# SPTSquidBoard.net
KiCad netlist of a schematic drawn in Altium Designer
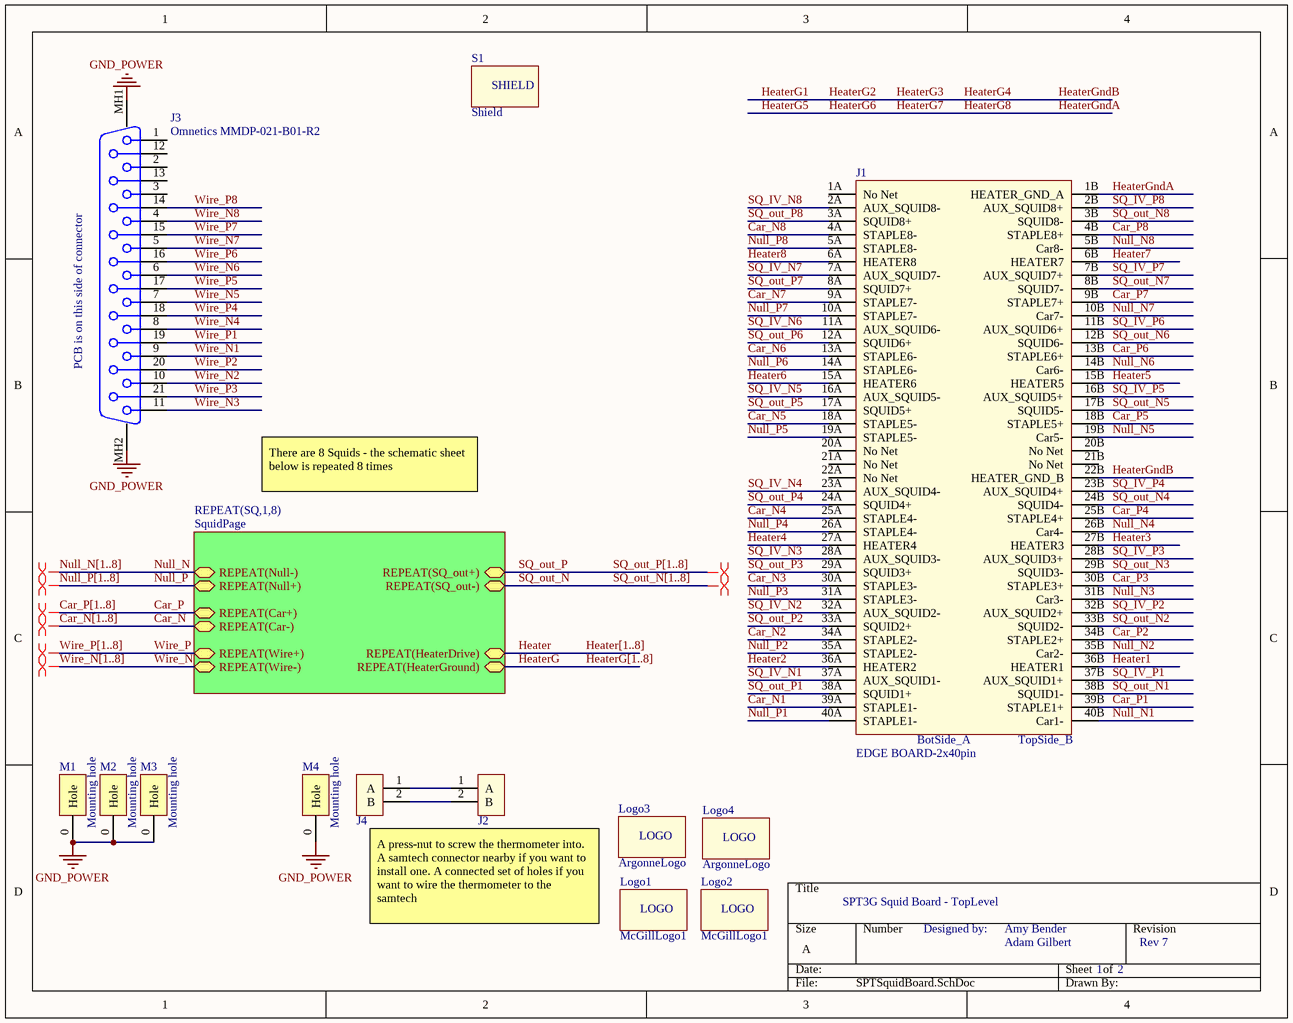
[diagram p0: SPTSquidBoard.SchDoc]

(export (version "E")
  (design (tool "Eeschema 10.0.6"))
  (components
    (comp (ref "J1")
      (value "EDGE BOARD-2x40pin")
      (description "Edge connector")
      (libsource (lib "SPT3G_LCBoard") (part "EDGE BOARD-2x40pin"))
    )
    (comp (ref "J2")
      (value "TempSenseWireConnection")
      (footprint "TempSenseWireCons")
      (libsource (lib "SPT3G_LCBoard") (part "TempSenseCon"))
    )
    (comp (ref "J3")
      (value "Omnetics MMDP-021-B01-R2")
      (footprint "MMDP-021-B02-R2")
      (description "OmneticsMicroD21")
      (libsource (lib "SPT3G_LCBoard") (part "OmneticsMicroD21"))
    )
    (comp (ref "J4")
      (value "TempSenseWireConnection")
      (footprint "TempSenseWireCons")
      (libsource (lib "") (part "TempSenseCon_1"))
    )
    (comp (ref "Logo1")
      (value "McGillLogo1")
      (footprint "McGillLogo1")
      (libsource (lib "SPT3G_LCBoard") (part "Logo"))
    )
    (comp (ref "Logo2")
      (value "McGillLogo1")
      (footprint "McGillLogo1")
      (libsource (lib "SPT3G_LCBoard") (part "Logo"))
    )
    (comp (ref "Logo3")
      (value "ArgonneLogo")
      (footprint "ArgonneLogo")
      (libsource (lib "SPT3G_AdapterBoard") (part "Logo"))
    )
    (comp (ref "Logo4")
      (value "ArgonneLogo")
      (footprint "ArgonneLogo")
      (libsource (lib "SPT3G_AdapterBoard") (part "Logo"))
    )
    (comp (ref "M1")
      (value "Mounting hole")
      (footprint "MountingHoleSquidBoard")
      (libsource (lib "SPT3G_LCBoard") (part "SquidBoardMountingHole"))
    )
    (comp (ref "M2")
      (value "Mounting hole")
      (footprint "MountingHoleSquidBoard")
      (libsource (lib "SPT3G_LCBoard") (part "SquidBoardMountingHole"))
    )
    (comp (ref "M3")
      (value "Mounting hole")
      (footprint "MountingHoleSquidBoard")
      (libsource (lib "SPT3G_LCBoard") (part "SquidBoardMountingHole"))
    )
    (comp (ref "M4")
      (value "Mounting hole")
      (footprint "MountingHoleSquidBoard")
      (libsource (lib "SPT3G_LCBoard") (part "SquidBoardMountingHole"))
    )
    (comp (ref "S1") (value "Shield") (footprint "Shield") (libsource (lib "SPT3G_LCBoard") (part "Shield")))
  )
  (nets
    (net (code "2") (name "/Car_N1") (class "Default")
      (node (ref "J1") (pin "39A") (pinfunction "STAPLE1-_39A") (pintype "passive"))
    )
    (net (code "3") (name "/Car_N2") (class "Default")
      (node (ref "J1") (pin "34A") (pinfunction "STAPLE2-_34A") (pintype "passive"))
    )
    (net (code "4") (name "/Car_N3") (class "Default")
      (node (ref "J1") (pin "30A") (pinfunction "STAPLE3-_30A") (pintype "passive"))
    )
    (net (code "5") (name "/Car_N4") (class "Default")
      (node (ref "J1") (pin "25A") (pinfunction "STAPLE4-_25A") (pintype "passive"))
    )
    (net (code "6") (name "/Car_N5") (class "Default")
      (node (ref "J1") (pin "18A") (pinfunction "STAPLE5-_18A") (pintype "passive"))
    )
    (net (code "7") (name "/Car_N6") (class "Default")
      (node (ref "J1") (pin "13A") (pinfunction "STAPLE6-_13A") (pintype "passive"))
    )
    (net (code "8") (name "/Car_N7") (class "Default")
      (node (ref "J1") (pin "9A") (pinfunction "STAPLE7-_9A") (pintype "passive"))
    )
    (net (code "9") (name "/Car_N8") (class "Default")
      (node (ref "J1") (pin "4A") (pinfunction "STAPLE8-_4A") (pintype "passive"))
    )
    (net (code "12") (name "/Car_P1") (class "Default")
      (node (ref "J1") (pin "39B") (pinfunction "STAPLE1+_39B") (pintype "passive"))
    )
    (net (code "13") (name "/Car_P2") (class "Default")
      (node (ref "J1") (pin "34B") (pinfunction "STAPLE2+_34B") (pintype "passive"))
    )
    (net (code "14") (name "/Car_P3") (class "Default")
      (node (ref "J1") (pin "30B") (pinfunction "STAPLE3+_30B") (pintype "passive"))
    )
    (net (code "15") (name "/Car_P4") (class "Default")
      (node (ref "J1") (pin "25B") (pinfunction "STAPLE4+_25B") (pintype "passive"))
    )
    (net (code "16") (name "/Car_P5") (class "Default")
      (node (ref "J1") (pin "18B") (pinfunction "STAPLE5+_18B") (pintype "passive"))
    )
    (net (code "17") (name "/Car_P6") (class "Default")
      (node (ref "J1") (pin "13B") (pinfunction "STAPLE6+_13B") (pintype "passive"))
    )
    (net (code "18") (name "/Car_P7") (class "Default")
      (node (ref "J1") (pin "9B") (pinfunction "STAPLE7+_9B") (pintype "passive"))
    )
    (net (code "19") (name "/Car_P8") (class "Default")
      (node (ref "J1") (pin "4B") (pinfunction "STAPLE8+_4B") (pintype "passive"))
    )
    (net (code "22") (name "/Heater1") (class "Default")
      (node (ref "J1") (pin "36B") (pinfunction "HEATER1_36B") (pintype "passive"))
    )
    (net (code "23") (name "/Heater2") (class "Default")
      (node (ref "J1") (pin "36A") (pinfunction "HEATER2_36A") (pintype "passive"))
    )
    (net (code "24") (name "/Heater3") (class "Default")
      (node (ref "J1") (pin "27B") (pinfunction "HEATER3_27B") (pintype "passive"))
    )
    (net (code "25") (name "/Heater4") (class "Default")
      (node (ref "J1") (pin "27A") (pinfunction "HEATER4_27A") (pintype "passive"))
    )
    (net (code "26") (name "/Heater5") (class "Default")
      (node (ref "J1") (pin "15B") (pinfunction "HEATER5_15B") (pintype "passive"))
    )
    (net (code "27") (name "/Heater6") (class "Default")
      (node (ref "J1") (pin "15A") (pinfunction "HEATER6_15A") (pintype "passive"))
    )
    (net (code "28") (name "/Heater7") (class "Default")
      (node (ref "J1") (pin "6B") (pinfunction "HEATER7_6B") (pintype "passive"))
    )
    (net (code "29") (name "/Heater8") (class "Default")
      (node (ref "J1") (pin "6A") (pinfunction "HEATER8_6A") (pintype "passive"))
    )
    (net (code "31") (name "/HeaterG4") (class "Default")
      (node (ref "J1") (pin "22B") (pinfunction "HEATER_GND_B_22B") (pintype "passive"))
    )
    (net (code "32") (name "/HeaterG8") (class "Default")
      (node (ref "J1") (pin "1B") (pinfunction "HEATER_GND_A_1B") (pintype "passive"))
    )
    (net (code "36") (name "/Null_N1") (class "Default")
      (node (ref "J1") (pin "40B") (pinfunction "Car1-_40B") (pintype "passive"))
    )
    (net (code "37") (name "/Null_N2") (class "Default")
      (node (ref "J1") (pin "35B") (pinfunction "Car2-_35B") (pintype "passive"))
    )
    (net (code "38") (name "/Null_N3") (class "Default")
      (node (ref "J1") (pin "31B") (pinfunction "Car3-_31B") (pintype "passive"))
    )
    (net (code "39") (name "/Null_N4") (class "Default")
      (node (ref "J1") (pin "26B") (pinfunction "Car4-_26B") (pintype "passive"))
    )
    (net (code "40") (name "/Null_N5") (class "Default")
      (node (ref "J1") (pin "19B") (pinfunction "Car5-_19B") (pintype "passive"))
    )
    (net (code "41") (name "/Null_N6") (class "Default")
      (node (ref "J1") (pin "14B") (pinfunction "Car6-_14B") (pintype "passive"))
    )
    (net (code "42") (name "/Null_N7") (class "Default")
      (node (ref "J1") (pin "10B") (pinfunction "Car7-_10B") (pintype "passive"))
    )
    (net (code "43") (name "/Null_N8") (class "Default")
      (node (ref "J1") (pin "5B") (pinfunction "Car8-_5B") (pintype "passive"))
    )
    (net (code "46") (name "/Null_P1") (class "Default")
      (node (ref "J1") (pin "40A") (pinfunction "STAPLE1-_40A") (pintype "passive"))
    )
    (net (code "47") (name "/Null_P2") (class "Default")
      (node (ref "J1") (pin "35A") (pinfunction "STAPLE2-_35A") (pintype "passive"))
    )
    (net (code "48") (name "/Null_P3") (class "Default")
      (node (ref "J1") (pin "31A") (pinfunction "STAPLE3-_31A") (pintype "passive"))
    )
    (net (code "49") (name "/Null_P4") (class "Default")
      (node (ref "J1") (pin "26A") (pinfunction "STAPLE4-_26A") (pintype "passive"))
    )
    (net (code "50") (name "/Null_P5") (class "Default")
      (node (ref "J1") (pin "19A") (pinfunction "STAPLE5-_19A") (pintype "passive"))
    )
    (net (code "51") (name "/Null_P6") (class "Default")
      (node (ref "J1") (pin "14A") (pinfunction "STAPLE6-_14A") (pintype "passive"))
    )
    (net (code "52") (name "/Null_P7") (class "Default")
      (node (ref "J1") (pin "10A") (pinfunction "STAPLE7-_10A") (pintype "passive"))
    )
    (net (code "53") (name "/Null_P8") (class "Default")
      (node (ref "J1") (pin "5A") (pinfunction "STAPLE8-_5A") (pintype "passive"))
    )
    (net (code "55") (name "/SQ_IV_N1") (class "Default")
      (node (ref "J1") (pin "37A") (pinfunction "AUX_SQUID1-_37A") (pintype "passive"))
    )
    (net (code "56") (name "/SQ_IV_N2") (class "Default")
      (node (ref "J1") (pin "32A") (pinfunction "AUX_SQUID2-_32A") (pintype "passive"))
    )
    (net (code "57") (name "/SQ_IV_N3") (class "Default")
      (node (ref "J1") (pin "28A") (pinfunction "AUX_SQUID3-_28A") (pintype "passive"))
    )
    (net (code "58") (name "/SQ_IV_N4") (class "Default")
      (node (ref "J1") (pin "23A") (pinfunction "AUX_SQUID4-_23A") (pintype "passive"))
    )
    (net (code "59") (name "/SQ_IV_N5") (class "Default")
      (node (ref "J1") (pin "16A") (pinfunction "AUX_SQUID5-_16A") (pintype "passive"))
    )
    (net (code "60") (name "/SQ_IV_N6") (class "Default")
      (node (ref "J1") (pin "11A") (pinfunction "AUX_SQUID6-_11A") (pintype "passive"))
    )
    (net (code "61") (name "/SQ_IV_N7") (class "Default")
      (node (ref "J1") (pin "7A") (pinfunction "AUX_SQUID7-_7A") (pintype "passive"))
    )
    (net (code "62") (name "/SQ_IV_N8") (class "Default")
      (node (ref "J1") (pin "2A") (pinfunction "AUX_SQUID8-_2A") (pintype "passive"))
    )
    (net (code "63") (name "/SQ_IV_P1") (class "Default")
      (node (ref "J1") (pin "37B") (pinfunction "AUX_SQUID1+_37B") (pintype "passive"))
    )
    (net (code "64") (name "/SQ_IV_P2") (class "Default")
      (node (ref "J1") (pin "32B") (pinfunction "AUX_SQUID2+_32B") (pintype "passive"))
    )
    (net (code "65") (name "/SQ_IV_P3") (class "Default")
      (node (ref "J1") (pin "28B") (pinfunction "AUX_SQUID3+_28B") (pintype "passive"))
    )
    (net (code "66") (name "/SQ_IV_P4") (class "Default")
      (node (ref "J1") (pin "23B") (pinfunction "AUX_SQUID4+_23B") (pintype "passive"))
    )
    (net (code "67") (name "/SQ_IV_P5") (class "Default")
      (node (ref "J1") (pin "16B") (pinfunction "AUX_SQUID5+_16B") (pintype "passive"))
    )
    (net (code "68") (name "/SQ_IV_P6") (class "Default")
      (node (ref "J1") (pin "11B") (pinfunction "AUX_SQUID6+_11B") (pintype "passive"))
    )
    (net (code "69") (name "/SQ_IV_P7") (class "Default")
      (node (ref "J1") (pin "7B") (pinfunction "AUX_SQUID7+_7B") (pintype "passive"))
    )
    (net (code "70") (name "/SQ_IV_P8") (class "Default")
      (node (ref "J1") (pin "2B") (pinfunction "AUX_SQUID8+_2B") (pintype "passive"))
    )
    (net (code "72") (name "/SQ_out_N1") (class "Default")
      (node (ref "J1") (pin "38B") (pinfunction "SQUID1-_38B") (pintype "passive"))
    )
    (net (code "73") (name "/SQ_out_N2") (class "Default")
      (node (ref "J1") (pin "33B") (pinfunction "SQUID2-_33B") (pintype "passive"))
    )
    (net (code "74") (name "/SQ_out_N3") (class "Default")
      (node (ref "J1") (pin "29B") (pinfunction "SQUID3-_29B") (pintype "passive"))
    )
    (net (code "75") (name "/SQ_out_N4") (class "Default")
      (node (ref "J1") (pin "24B") (pinfunction "SQUID4-_24B") (pintype "passive"))
    )
    (net (code "76") (name "/SQ_out_N5") (class "Default")
      (node (ref "J1") (pin "17B") (pinfunction "SQUID5-_17B") (pintype "passive"))
    )
    (net (code "77") (name "/SQ_out_N6") (class "Default")
      (node (ref "J1") (pin "12B") (pinfunction "SQUID6-_12B") (pintype "passive"))
    )
    (net (code "78") (name "/SQ_out_N7") (class "Default")
      (node (ref "J1") (pin "8B") (pinfunction "SQUID7-_8B") (pintype "passive"))
    )
    (net (code "79") (name "/SQ_out_N8") (class "Default")
      (node (ref "J1") (pin "3B") (pinfunction "SQUID8-_3B") (pintype "passive"))
    )
    (net (code "82") (name "/SQ_out_P1") (class "Default")
      (node (ref "J1") (pin "38A") (pinfunction "SQUID1+_38A") (pintype "passive"))
    )
    (net (code "83") (name "/SQ_out_P2") (class "Default")
      (node (ref "J1") (pin "33A") (pinfunction "SQUID2+_33A") (pintype "passive"))
    )
    (net (code "84") (name "/SQ_out_P3") (class "Default")
      (node (ref "J1") (pin "29A") (pinfunction "SQUID3+_29A") (pintype "passive"))
    )
    (net (code "85") (name "/SQ_out_P4") (class "Default")
      (node (ref "J1") (pin "24A") (pinfunction "SQUID4+_24A") (pintype "passive"))
    )
    (net (code "86") (name "/SQ_out_P5") (class "Default")
      (node (ref "J1") (pin "17A") (pinfunction "SQUID5+_17A") (pintype "passive"))
    )
    (net (code "87") (name "/SQ_out_P6") (class "Default")
      (node (ref "J1") (pin "12A") (pinfunction "SQUID6+_12A") (pintype "passive"))
    )
    (net (code "88") (name "/SQ_out_P7") (class "Default")
      (node (ref "J1") (pin "8A") (pinfunction "SQUID7+_8A") (pintype "passive"))
    )
    (net (code "89") (name "/SQ_out_P8") (class "Default")
      (node (ref "J1") (pin "3A") (pinfunction "SQUID8+_3A") (pintype "passive"))
    )
    (net (code "92") (name "/Wire_N1") (class "Default")
      (node (ref "J3") (pin "9") (pinfunction "9_9") (pintype "passive"))
    )
    (net (code "93") (name "/Wire_N2") (class "Default")
      (node (ref "J3") (pin "10") (pinfunction "10_10") (pintype "passive"))
    )
    (net (code "94") (name "/Wire_N3") (class "Default")
      (node (ref "J3") (pin "11") (pinfunction "11_11") (pintype "passive"))
    )
    (net (code "95") (name "/Wire_N4") (class "Default")
      (node (ref "J3") (pin "8") (pinfunction "8_8") (pintype "passive"))
    )
    (net (code "96") (name "/Wire_N5") (class "Default")
      (node (ref "J3") (pin "7") (pinfunction "7_7") (pintype "passive"))
    )
    (net (code "97") (name "/Wire_N6") (class "Default")
      (node (ref "J3") (pin "6") (pinfunction "6_6") (pintype "passive"))
    )
    (net (code "98") (name "/Wire_N7") (class "Default")
      (node (ref "J3") (pin "5") (pinfunction "5_5") (pintype "passive"))
    )
    (net (code "99") (name "/Wire_N8") (class "Default")
      (node (ref "J3") (pin "4") (pinfunction "4_4") (pintype "passive"))
    )
    (net (code "102") (name "/Wire_P1") (class "Default")
      (node (ref "J3") (pin "19") (pinfunction "19_19") (pintype "passive"))
    )
    (net (code "103") (name "/Wire_P2") (class "Default")
      (node (ref "J3") (pin "20") (pinfunction "20_20") (pintype "passive"))
    )
    (net (code "104") (name "/Wire_P3") (class "Default")
      (node (ref "J3") (pin "21") (pinfunction "21_21") (pintype "passive"))
    )
    (net (code "105") (name "/Wire_P4") (class "Default")
      (node (ref "J3") (pin "18") (pinfunction "18_18") (pintype "passive"))
    )
    (net (code "106") (name "/Wire_P5") (class "Default")
      (node (ref "J3") (pin "17") (pinfunction "17_17") (pintype "passive"))
    )
    (net (code "107") (name "/Wire_P6") (class "Default")
      (node (ref "J3") (pin "16") (pinfunction "16_16") (pintype "passive"))
    )
    (net (code "108") (name "/Wire_P7") (class "Default")
      (node (ref "J3") (pin "15") (pinfunction "15_15") (pintype "passive"))
    )
    (net (code "109") (name "/Wire_P8") (class "Default")
      (node (ref "J3") (pin "14") (pinfunction "14_14") (pintype "passive"))
    )
    (net (code "111") (name "GND_POWER") (class "Default")
      (node (ref "J3") (pin "MH1") (pinfunction "MH1_MH1") (pintype "passive"))
      (node (ref "J3") (pin "MH2") (pinfunction "MH2_MH2") (pintype "passive"))
      (node (ref "M1") (pin "0") (pinfunction "Hole_0") (pintype "passive"))
      (node (ref "M2") (pin "0") (pinfunction "Hole_0") (pintype "passive"))
      (node (ref "M3") (pin "0") (pinfunction "Hole_0") (pintype "passive"))
      (node (ref "M4") (pin "0") (pinfunction "Hole_0") (pintype "passive"))
    )
    (net (code "112") (name "Net-(J2-A)") (class "Default")
      (node (ref "J2") (pin "1") (pinfunction "A_1") (pintype "passive"))
      (node (ref "J4") (pin "1") (pinfunction "A_1") (pintype "passive"))
    )
    (net (code "113") (name "Net-(J2-B)") (class "Default")
      (node (ref "J2") (pin "2") (pinfunction "B_2") (pintype "passive"))
      (node (ref "J4") (pin "2") (pinfunction "B_2") (pintype "passive"))
    )
    (net (code "114") (name "unconnected-(J1-No_Net-Pad1A)") (class "Default")
      (node (ref "J1") (pin "1A") (pinfunction "No_Net_1A") (pintype "passive"))
    )
    (net (code "115") (name "unconnected-(J1-No_Net-Pad20A)") (class "Default")
      (node (ref "J1") (pin "20A") (pinfunction "No_Net_20A") (pintype "passive"))
    )
    (net (code "116") (name "unconnected-(J1-No_Net-Pad20B)") (class "Default")
      (node (ref "J1") (pin "20B") (pinfunction "No_Net_20B") (pintype "passive"))
    )
    (net (code "117") (name "unconnected-(J1-No_Net-Pad21A)") (class "Default")
      (node (ref "J1") (pin "21A") (pinfunction "No_Net_21A") (pintype "passive"))
    )
    (net (code "118") (name "unconnected-(J1-No_Net-Pad21B)") (class "Default")
      (node (ref "J1") (pin "21B") (pinfunction "No_Net_21B") (pintype "passive"))
    )
    (net (code "119") (name "unconnected-(J1-No_Net-Pad22A)") (class "Default")
      (node (ref "J1") (pin "22A") (pinfunction "No_Net_22A") (pintype "passive"))
    )
    (net (code "120") (name "unconnected-(J3-Pad1)") (class "Default")
      (node (ref "J3") (pin "1") (pinfunction "1_1") (pintype "passive"))
    )
    (net (code "121") (name "unconnected-(J3-Pad2)") (class "Default")
      (node (ref "J3") (pin "2") (pinfunction "2_2") (pintype "passive"))
    )
    (net (code "122") (name "unconnected-(J3-Pad3)") (class "Default")
      (node (ref "J3") (pin "3") (pinfunction "3_3") (pintype "passive"))
    )
    (net (code "123") (name "unconnected-(J3-Pad12)") (class "Default")
      (node (ref "J3") (pin "12") (pinfunction "12_12") (pintype "passive"))
    )
    (net (code "124") (name "unconnected-(J3-Pad13)") (class "Default")
      (node (ref "J3") (pin "13") (pinfunction "13_13") (pintype "passive"))
    )
  )
)
